# Power.net
KiCad netlist of a schematic drawn in Altium Designer
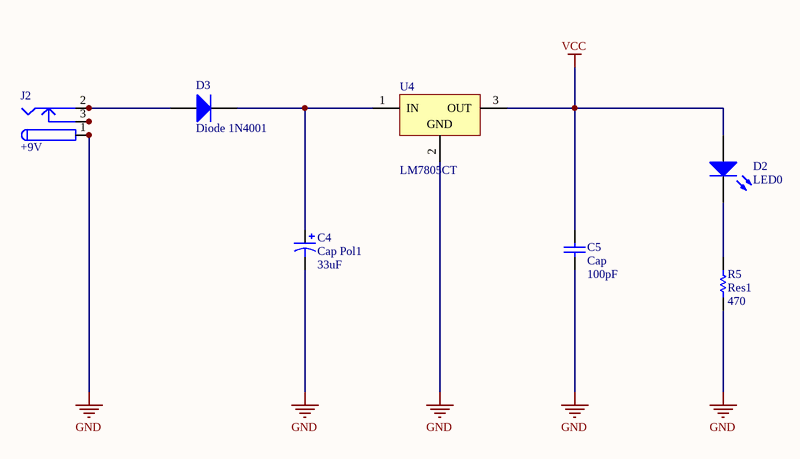
[diagram p0: Power.SchDoc]

(export (version "E")
  (design (tool "Eeschema 10.0.6"))
  (components
    (comp (ref "C4")
      (value "Cap Pol1")
      (footprint "RB7.6-15")
      (description "Polarized Capacitor (Radial)")
      (fields (field (name "ALTIUM_VALUE") "33uF") (field (name "PUBLISHER") "Altium Limited"))
      (libsource (lib "Chap-7-实践题(1)") (part "Cap Pol1"))
    )
    (comp (ref "C5")
      (value "Cap")
      (footprint "RAD-0.3")
      (description "Capacitor")
      (fields (field (name "ALTIUM_VALUE") "100pF") (field (name "PUBLISHER") "Altium Limited"))
      (libsource (lib "Chap-7-实践题(1)") (part "Cap"))
    )
    (comp (ref "D2")
      (value "LED0")
      (footprint "LED-0")
      (description "Typical INFRARED GaAs LED")
      (fields (field (name "PUBLISHER") "Altium Limited"))
      (libsource (lib "Chap-7-实践题(1)") (part "LED0"))
    )
    (comp (ref "D3")
      (value "Diode 1N4001")
      (footprint "DO-41")
      (description "1 Amp General Purpose Rectifier")
      (fields (field (name "PUBLISHER") "Altium Limited"))
      (libsource (lib "Chap-7-实践题(1)") (part "Diode 1N4001"))
    )
    (comp (ref "J2")
      (value "+9V")
      (footprint "KLD-0202")
      (description "Low Voltage Power Supply Connector")
      (fields (field (name "PUBLISHER") "Altium Limited"))
      (libsource (lib "Chap-7-实践题(1)") (part "PWR2.5"))
    )
    (comp (ref "R5")
      (value "Res1")
      (footprint "AXIAL-0.3")
      (description "Resistor")
      (fields (field (name "ALTIUM_VALUE") "470") (field (name "PUBLISHER") "Altium Limited"))
      (libsource (lib "Chap-7-实践题(1)") (part "Res1"))
    )
    (comp (ref "U4")
      (value "LM7805CT")
      (footprint "T03B")
      (description "Series 3-Terminal Positive Regulator")
      (fields (field (name "PUBLISHER") "Altium Limited"))
      (libsource (lib "Chap-7-实践题(1)") (part "LM7818CT"))
    )
  )
  (nets
    (net (code "1") (name "GND") (class "Default")
      (node (ref "C4") (pin "2") (pinfunction "2_2") (pintype "passive"))
      (node (ref "C5") (pin "1") (pinfunction "1_1") (pintype "passive"))
      (node (ref "J2") (pin "1") (pinfunction "1_1") (pintype "power_in"))
      (node (ref "J2") (pin "1A") (pinfunction "1A_1A") (pintype "power_in"))
      (node (ref "J2") (pin "1B") (pinfunction "1B_1B") (pintype "power_in"))
      (node (ref "R5") (pin "1") (pinfunction "1_1") (pintype "passive"))
      (node (ref "U4") (pin "2") (pinfunction "GND_2") (pintype "power_in"))
    )
    (net (code "2") (name "Net-(D2-K)") (class "Default")
      (node (ref "D2") (pin "2") (pinfunction "K_2") (pintype "passive"))
      (node (ref "R5") (pin "2") (pinfunction "2_2") (pintype "passive"))
    )
    (net (code "3") (name "Net-(D3-A)") (class "Default")
      (node (ref "D3") (pin "1") (pinfunction "A_1") (pintype "passive"))
      (node (ref "J2") (pin "2") (pinfunction "2_2") (pintype "power_in"))
      (node (ref "J2") (pin "2A") (pinfunction "2A_2A") (pintype "power_in"))
      (node (ref "J2") (pin "2B") (pinfunction "2B_2B") (pintype "power_in"))
    )
    (net (code "4") (name "Net-(D3-K)") (class "Default")
      (node (ref "C4") (pin "1") (pinfunction "1_1") (pintype "passive"))
      (node (ref "D3") (pin "2") (pinfunction "K_2") (pintype "passive"))
      (node (ref "U4") (pin "1") (pinfunction "IN_1") (pintype "power_in"))
    )
    (net (code "5") (name "Net-(J2-Pad3)") (class "Default")
      (node (ref "J2") (pin "3") (pinfunction "3_3") (pintype "power_in"))
      (node (ref "J2") (pin "3A") (pinfunction "3A_3A") (pintype "power_in"))
      (node (ref "J2") (pin "3B") (pinfunction "3B_3B") (pintype "power_in"))
    )
    (net (code "6") (name "VCC") (class "Default")
      (node (ref "C5") (pin "2") (pinfunction "2_2") (pintype "passive"))
      (node (ref "D2") (pin "1") (pinfunction "A_1") (pintype "passive"))
      (node (ref "U4") (pin "3") (pinfunction "OUT_3") (pintype "power_in"))
    )
  )
)
